# Atmega8a_dev_board.net
KiCad netlist of a schematic drawn in Altium Designer
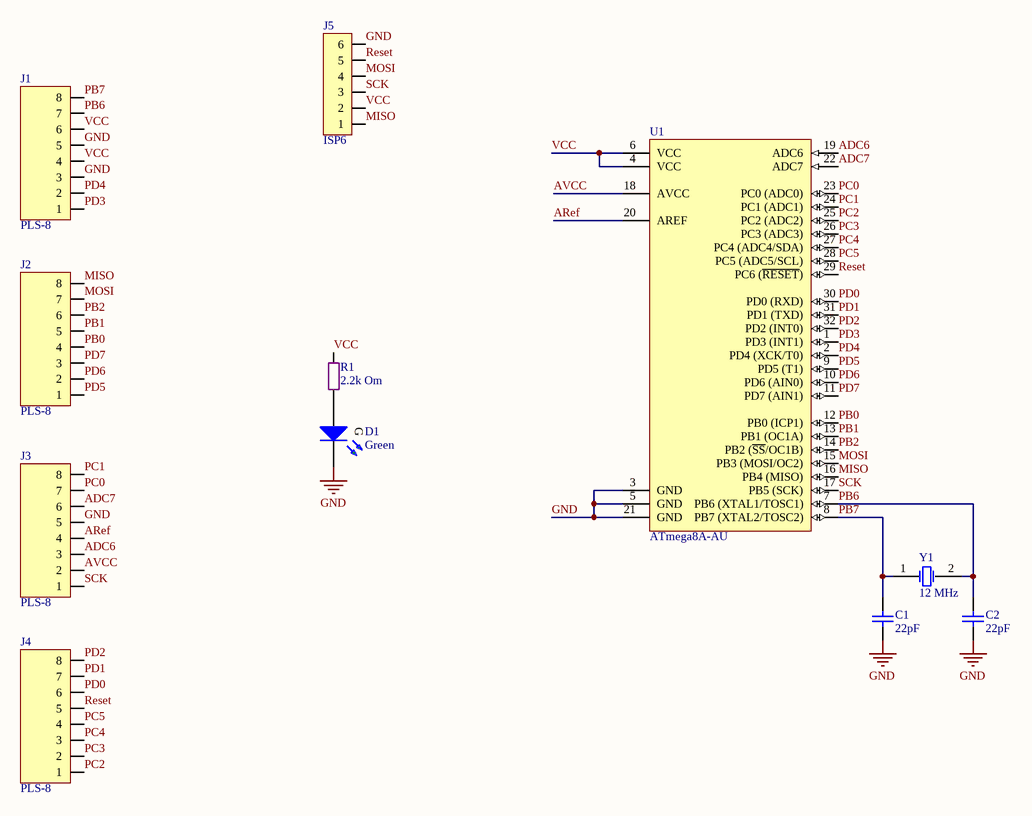
[diagram p0: Atmega8a dev board.SchDoc]

(export (version "E")
  (design (tool "Eeschema 10.0.6"))
  (components
    (comp (ref "C1")
      (value "22pF")
      (footprint "Capacitor:SMD 0805 (2012)")
      (description "Capacitor")
      (libsource (lib "Capacitor") (part "Cap SMD 0402-1812"))
    )
    (comp (ref "C2")
      (value "22pF")
      (footprint "Capacitor:SMD 0805 (2012)")
      (description "Capacitor")
      (libsource (lib "Capacitor") (part "Cap SMD 0402-1812"))
    )
    (comp (ref "D1")
      (value "Green")
      (footprint "LED:LED SMD 0805 Green")
      (description "?2v ?20mA")
      (libsource (lib "LED") (part "Led SMD 0805 Green"))
    )
    (comp (ref "J1")
      (value "PLS-8")
      (footprint "Connector:Line 2.54 x 8")
      (description "Vert, Sgl line, Male")
      (libsource (lib "Connector") (part "PLS-8"))
    )
    (comp (ref "J2")
      (value "PLS-8")
      (footprint "Connector:Line 2.54 x 8")
      (description "Vert, Sgl line, Male")
      (libsource (lib "Connector") (part "PLS-8"))
    )
    (comp (ref "J3")
      (value "PLS-8")
      (footprint "Connector:Line 2.54 x 8")
      (description "Vert, Sgl line, Male")
      (libsource (lib "Connector") (part "PLS-8"))
    )
    (comp (ref "J4")
      (value "PLS-8")
      (footprint "Connector:Line 2.54 x 8")
      (description "Vert, Sgl line, Male")
      (libsource (lib "Connector") (part "PLS-8"))
    )
    (comp (ref "J5")
      (value "ISP6")
      (footprint "Connector:LINE 2.54 x 6D (2 x 3)")
      (description "Vert, Dbl line, Male")
      (libsource (lib "Connector") (part "PLD-6 (2 x 3)"))
    )
    (comp (ref "R1")
      (value "2.2k Om")
      (footprint "PassiveComponents:SMD 0805 (2012)")
      (libsource (lib "PassiveComponents") (part "Res All Types"))
    )
    (comp (ref "U1")
      (value "ATmega8A-AU")
      (footprint "32A_M")
      (fields (field (name "PUBLISHER") "Altium Limited"))
      (libsource (lib "Atmel Microcontroller 8-Bit megaAVR") (part "ATmega8A-AU"))
    )
    (comp (ref "Y1")
      (value "12 MHz")
      (footprint "PassiveComponents:XTAL - 2")
      (description "Crystal Oscillator")
      (fields (field (name "PUBLISHER") "Altium Limited"))
      (libsource (lib "PassiveComponents") (part "XTAL"))
    )
  )
  (nets
    (net (code "1") (name "/ADC6") (class "Default")
      (node (ref "J3") (pin "3") (pinfunction "3_3") (pintype "passive"))
      (node (ref "U1") (pin "19") (pinfunction "ADC6_19") (pintype "input"))
    )
    (net (code "2") (name "/ADC7") (class "Default")
      (node (ref "J3") (pin "6") (pinfunction "6_6") (pintype "passive"))
      (node (ref "U1") (pin "22") (pinfunction "ADC7_22") (pintype "input"))
    )
    (net (code "3") (name "/ARef") (class "Default")
      (node (ref "J3") (pin "4") (pinfunction "4_4") (pintype "passive"))
      (node (ref "U1") (pin "20") (pinfunction "AREF_20") (pintype "power_in"))
    )
    (net (code "4") (name "/AVCC") (class "Default")
      (node (ref "J3") (pin "2") (pinfunction "2_2") (pintype "passive"))
      (node (ref "U1") (pin "18") (pinfunction "AVCC_18") (pintype "power_in"))
    )
    (net (code "5") (name "/MISO") (class "Default")
      (node (ref "J2") (pin "8") (pinfunction "8_8") (pintype "passive"))
      (node (ref "J5") (pin "1") (pinfunction "1_1") (pintype "passive"))
      (node (ref "U1") (pin "16") (pinfunction "PB4_(MISO)_16") (pintype "bidirectional"))
    )
    (net (code "6") (name "/MOSI") (class "Default")
      (node (ref "J2") (pin "7") (pinfunction "7_7") (pintype "passive"))
      (node (ref "J5") (pin "4") (pinfunction "4_4") (pintype "passive"))
      (node (ref "U1") (pin "15") (pinfunction "PB3_(MOSI/OC2)_15") (pintype "bidirectional"))
    )
    (net (code "7") (name "/PB0") (class "Default")
      (node (ref "J2") (pin "4") (pinfunction "4_4") (pintype "passive"))
      (node (ref "U1") (pin "12") (pinfunction "PB0_(ICP1)_12") (pintype "bidirectional"))
    )
    (net (code "8") (name "/PB1") (class "Default")
      (node (ref "J2") (pin "5") (pinfunction "5_5") (pintype "passive"))
      (node (ref "U1") (pin "13") (pinfunction "PB1_(OC1A)_13") (pintype "bidirectional"))
    )
    (net (code "9") (name "/PB2") (class "Default")
      (node (ref "J2") (pin "6") (pinfunction "6_6") (pintype "passive"))
      (node (ref "U1") (pin "14") (pinfunction "PB2_(~{SS}/OC1B)_14") (pintype "bidirectional"))
    )
    (net (code "10") (name "/PB6") (class "Default")
      (node (ref "C2") (pin "2") (pinfunction "2_2") (pintype "passive"))
      (node (ref "J1") (pin "7") (pinfunction "7_7") (pintype "passive"))
      (node (ref "U1") (pin "7") (pinfunction "PB6_(XTAL1/TOSC1)_7") (pintype "bidirectional"))
      (node (ref "Y1") (pin "2") (pinfunction "OSC2_2") (pintype "passive"))
    )
    (net (code "11") (name "/PB7") (class "Default")
      (node (ref "C1") (pin "2") (pinfunction "2_2") (pintype "passive"))
      (node (ref "J1") (pin "8") (pinfunction "8_8") (pintype "passive"))
      (node (ref "U1") (pin "8") (pinfunction "PB7_(XTAL2/TOSC2)_8") (pintype "bidirectional"))
      (node (ref "Y1") (pin "1") (pinfunction "OSC1_1") (pintype "passive"))
    )
    (net (code "12") (name "/PC0") (class "Default")
      (node (ref "J3") (pin "7") (pinfunction "7_7") (pintype "passive"))
      (node (ref "U1") (pin "23") (pinfunction "PC0_(ADC0)_23") (pintype "bidirectional"))
    )
    (net (code "13") (name "/PC1") (class "Default")
      (node (ref "J3") (pin "8") (pinfunction "8_8") (pintype "passive"))
      (node (ref "U1") (pin "24") (pinfunction "PC1_(ADC1)_24") (pintype "bidirectional"))
    )
    (net (code "14") (name "/PC2") (class "Default")
      (node (ref "J4") (pin "1") (pinfunction "1_1") (pintype "passive"))
      (node (ref "U1") (pin "25") (pinfunction "PC2_(ADC2)_25") (pintype "bidirectional"))
    )
    (net (code "15") (name "/PC3") (class "Default")
      (node (ref "J4") (pin "2") (pinfunction "2_2") (pintype "passive"))
      (node (ref "U1") (pin "26") (pinfunction "PC3_(ADC3)_26") (pintype "bidirectional"))
    )
    (net (code "16") (name "/PC4") (class "Default")
      (node (ref "J4") (pin "3") (pinfunction "3_3") (pintype "passive"))
      (node (ref "U1") (pin "27") (pinfunction "PC4_(ADC4/SDA)_27") (pintype "bidirectional"))
    )
    (net (code "17") (name "/PC5") (class "Default")
      (node (ref "J4") (pin "4") (pinfunction "4_4") (pintype "passive"))
      (node (ref "U1") (pin "28") (pinfunction "PC5_(ADC5/SCL)_28") (pintype "bidirectional"))
    )
    (net (code "18") (name "/PD0") (class "Default")
      (node (ref "J4") (pin "6") (pinfunction "6_6") (pintype "passive"))
      (node (ref "U1") (pin "30") (pinfunction "PD0_(RXD)_30") (pintype "bidirectional"))
    )
    (net (code "19") (name "/PD1") (class "Default")
      (node (ref "J4") (pin "7") (pinfunction "7_7") (pintype "passive"))
      (node (ref "U1") (pin "31") (pinfunction "PD1_(TXD)_31") (pintype "bidirectional"))
    )
    (net (code "20") (name "/PD2") (class "Default")
      (node (ref "J4") (pin "8") (pinfunction "8_8") (pintype "passive"))
      (node (ref "U1") (pin "32") (pinfunction "PD2_(INT0)_32") (pintype "bidirectional"))
    )
    (net (code "21") (name "/PD3") (class "Default")
      (node (ref "J1") (pin "1") (pinfunction "1_1") (pintype "passive"))
      (node (ref "U1") (pin "1") (pinfunction "PD3_(INT1)_1") (pintype "bidirectional"))
    )
    (net (code "22") (name "/PD4") (class "Default")
      (node (ref "J1") (pin "2") (pinfunction "2_2") (pintype "passive"))
      (node (ref "U1") (pin "2") (pinfunction "PD4_(XCK/T0)_2") (pintype "bidirectional"))
    )
    (net (code "23") (name "/PD5") (class "Default")
      (node (ref "J2") (pin "1") (pinfunction "1_1") (pintype "passive"))
      (node (ref "U1") (pin "9") (pinfunction "PD5_(T1)_9") (pintype "bidirectional"))
    )
    (net (code "24") (name "/PD6") (class "Default")
      (node (ref "J2") (pin "2") (pinfunction "2_2") (pintype "passive"))
      (node (ref "U1") (pin "10") (pinfunction "PD6_(AIN0)_10") (pintype "bidirectional"))
    )
    (net (code "25") (name "/PD7") (class "Default")
      (node (ref "J2") (pin "3") (pinfunction "3_3") (pintype "passive"))
      (node (ref "U1") (pin "11") (pinfunction "PD7_(AIN1)_11") (pintype "bidirectional"))
    )
    (net (code "26") (name "/Reset") (class "Default")
      (node (ref "J4") (pin "5") (pinfunction "5_5") (pintype "passive"))
      (node (ref "J5") (pin "5") (pinfunction "5_5") (pintype "passive"))
      (node (ref "U1") (pin "29") (pinfunction "PC6_(~{RESET})_29") (pintype "bidirectional"))
    )
    (net (code "27") (name "/SCK") (class "Default")
      (node (ref "J3") (pin "1") (pinfunction "1_1") (pintype "passive"))
      (node (ref "J5") (pin "3") (pinfunction "3_3") (pintype "passive"))
      (node (ref "U1") (pin "17") (pinfunction "PB5_(SCK)_17") (pintype "bidirectional"))
    )
    (net (code "28") (name "/VCC") (class "Default")
      (node (ref "J1") (pin "4") (pinfunction "4_4") (pintype "passive"))
      (node (ref "J1") (pin "6") (pinfunction "6_6") (pintype "passive"))
      (node (ref "J5") (pin "2") (pinfunction "2_2") (pintype "passive"))
      (node (ref "R1") (pin "1") (pinfunction "1_1") (pintype "passive"))
      (node (ref "U1") (pin "4") (pinfunction "VCC_4") (pintype "power_in"))
      (node (ref "U1") (pin "6") (pinfunction "VCC_6") (pintype "power_in"))
    )
    (net (code "29") (name "GND") (class "Default")
      (node (ref "C1") (pin "1") (pinfunction "1_1") (pintype "passive"))
      (node (ref "C2") (pin "1") (pinfunction "1_1") (pintype "passive"))
      (node (ref "D1") (pin "K") (pinfunction "K_K") (pintype "passive"))
      (node (ref "J1") (pin "3") (pinfunction "3_3") (pintype "passive"))
      (node (ref "J1") (pin "5") (pinfunction "5_5") (pintype "passive"))
      (node (ref "J3") (pin "5") (pinfunction "5_5") (pintype "passive"))
      (node (ref "J5") (pin "6") (pinfunction "6_6") (pintype "passive"))
      (node (ref "U1") (pin "21") (pinfunction "GND_21") (pintype "power_in"))
      (node (ref "U1") (pin "3") (pinfunction "GND_3") (pintype "power_in"))
      (node (ref "U1") (pin "5") (pinfunction "GND_5") (pintype "power_in"))
    )
    (net (code "30") (name "Net-(D1-PadA)") (class "Default")
      (node (ref "D1") (pin "A") (pinfunction "A_A") (pintype "passive"))
      (node (ref "R1") (pin "2") (pinfunction "2_2") (pintype "passive"))
    )
  )
)
